# Ada_-_Base_Block_-_Microcontroller_Issue.net
KiCad netlist of a schematic drawn in Altium Designer
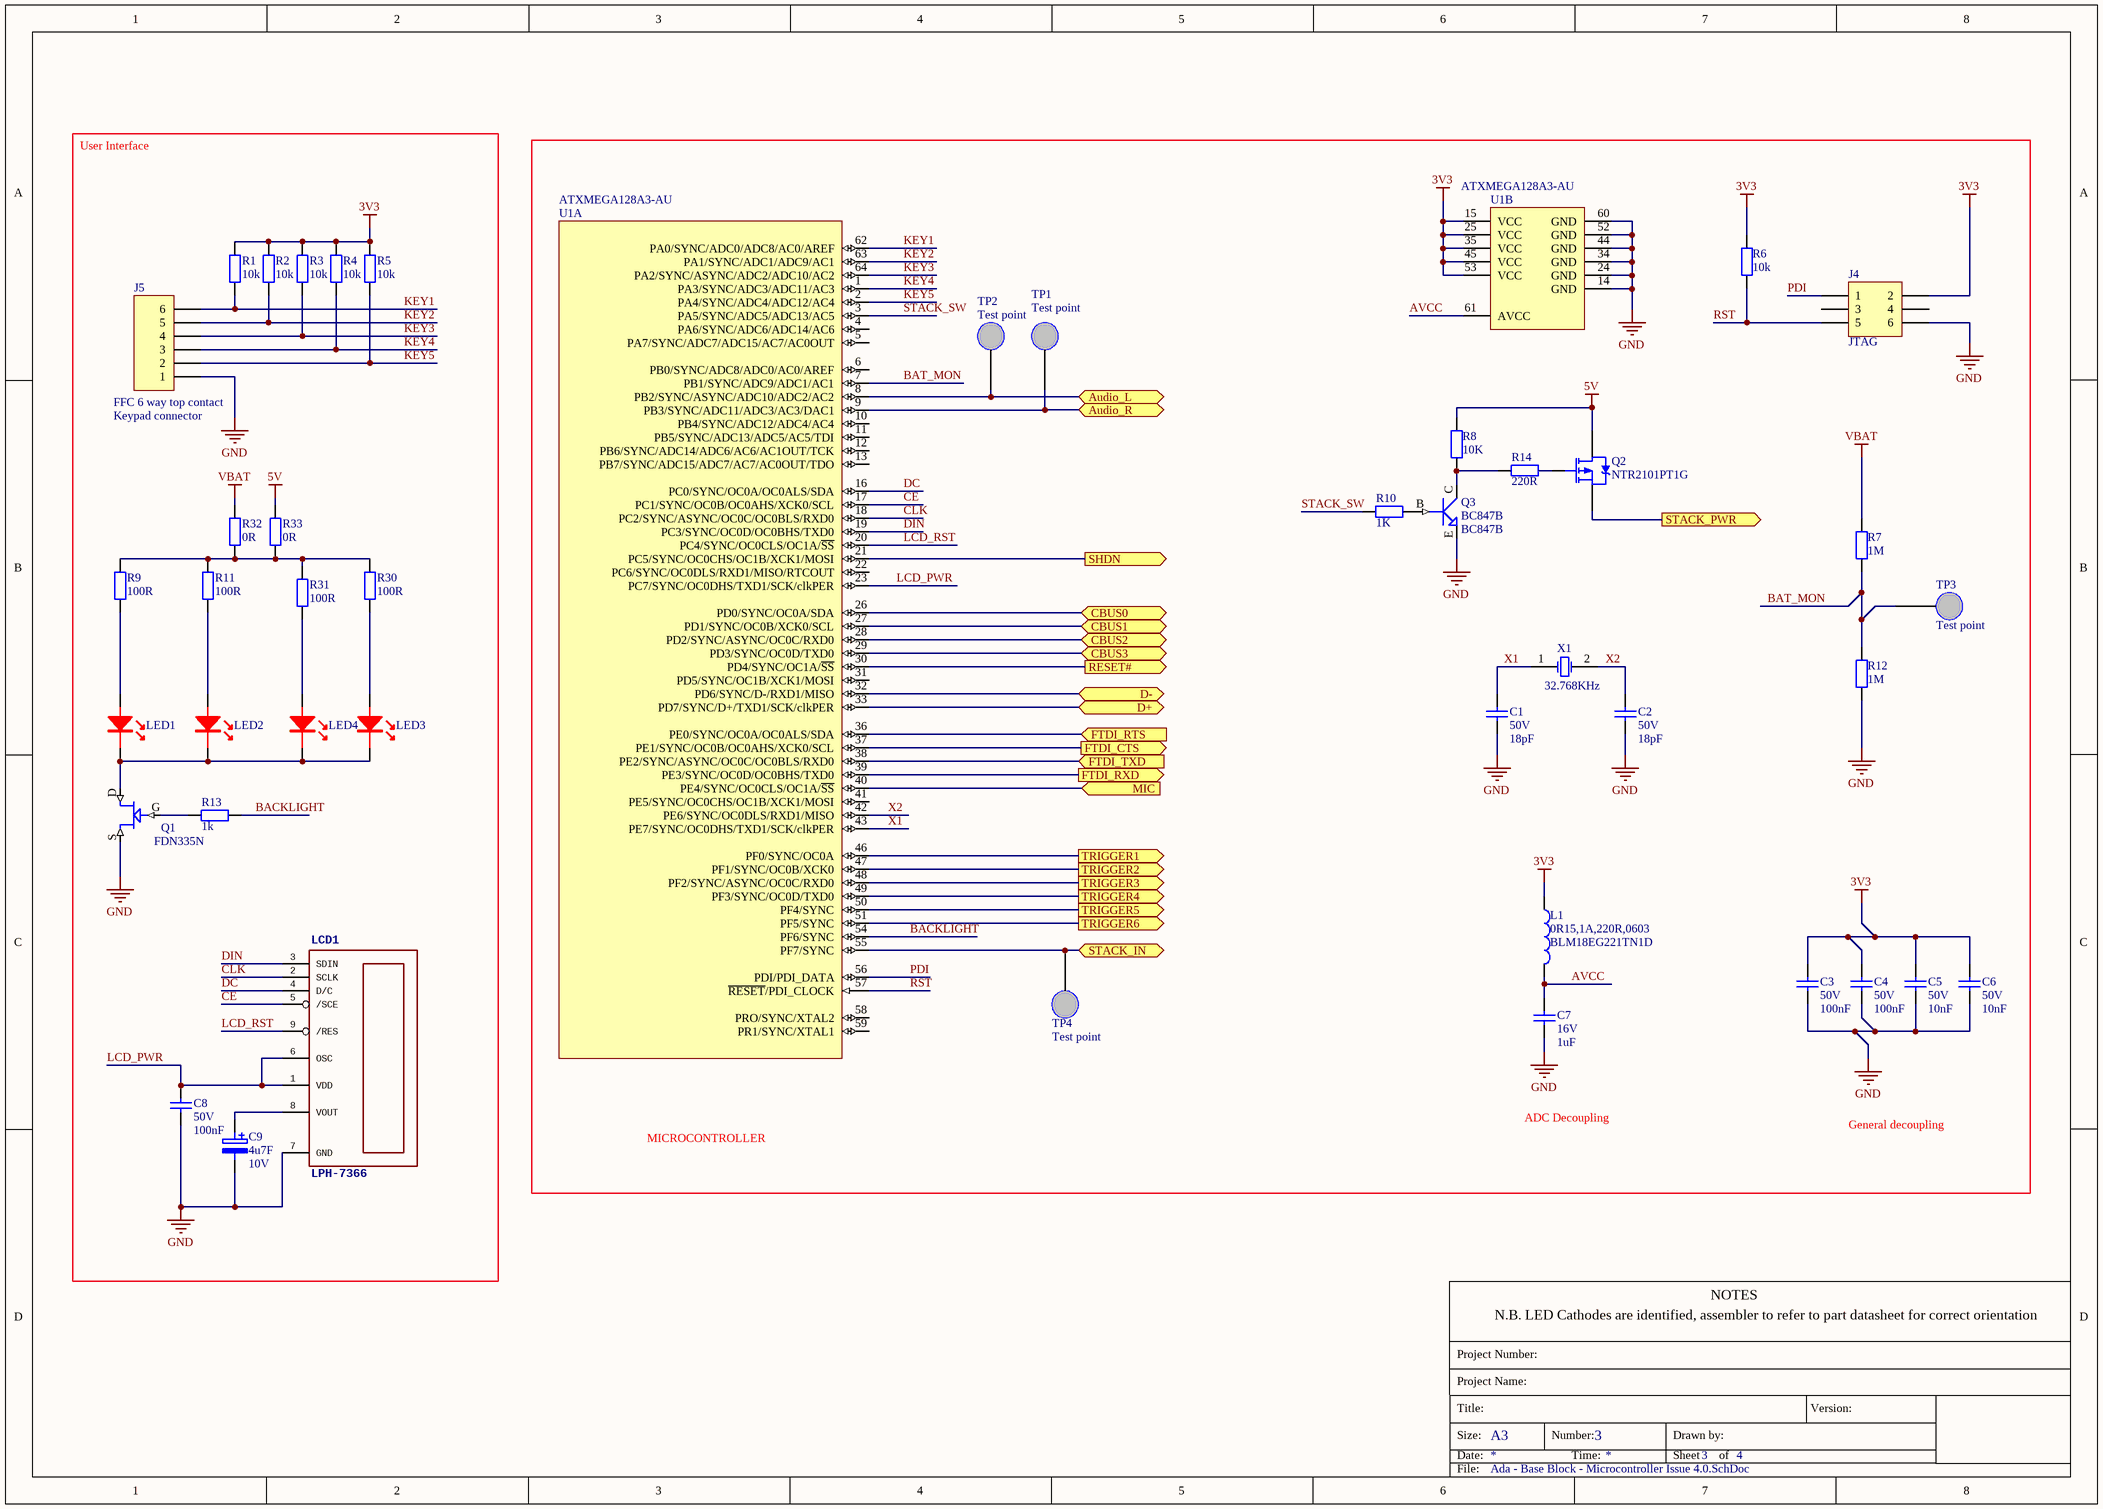
[diagram p0: Ada - Base Block - Microcontroller Issue 4.0.SchDoc]

(export (version "E")
  (design (tool "Eeschema 10.0.6"))
  (components
    (comp (ref "C1")
      (value "18pF")
      (footprint "C0603")
      (description "Ceramic")
      (fields
        (field (name "MANUFACTURER") "KEMET")
        (field (name "MANUF PART #") "C0603C180J5GAC")
        (field (name "VOLTAGE") "50V")
      )
      (libsource (lib "Capacitors") (part "18pF, 50V, 0603"))
    )
    (comp (ref "C2")
      (value "18pF")
      (footprint "C0603")
      (description "Ceramic")
      (fields
        (field (name "MANUFACTURER") "KEMET")
        (field (name "MANUF PART #") "C0603C180J5GAC")
        (field (name "VOLTAGE") "50V")
      )
      (libsource (lib "Capacitors") (part "18pF, 50V, 0603"))
    )
    (comp (ref "C3")
      (value "100nF")
      (footprint "C0603")
      (description "Ceramic")
      (fields
        (field (name "MANUFACTURER") "TruCap")
        (field (name "MANUF PART #") "U0603R103")
        (field (name "VOLTAGE") "50V")
      )
      (libsource (lib "Capacitors") (part "100nF, 16V, 0603"))
    )
    (comp (ref "C4")
      (value "100nF")
      (footprint "C0603")
      (description "Ceramic")
      (fields
        (field (name "MANUFACTURER") "TruCap")
        (field (name "MANUF PART #") "U0603R103")
        (field (name "VOLTAGE") "50V")
      )
      (libsource (lib "Capacitors") (part "100nF, 16V, 0603"))
    )
    (comp (ref "C5")
      (value "10nF")
      (footprint "C0603")
      (description "Ceramic")
      (fields
        (field (name "MANUFACTURER") "MULTICOMP")
        (field (name "MANUF PART #") "MCCA000238")
        (field (name "VOLTAGE") "50V")
      )
      (libsource (lib "Capacitors") (part "10nF, 50V, 0603"))
    )
    (comp (ref "C6")
      (value "10nF")
      (footprint "C0603")
      (description "Ceramic")
      (fields
        (field (name "MANUFACTURER") "MULTICOMP")
        (field (name "MANUF PART #") "MCCA000238")
        (field (name "VOLTAGE") "50V")
      )
      (libsource (lib "Capacitors") (part "10nF, 50V, 0603"))
    )
    (comp (ref "C7")
      (value "1uF")
      (footprint "C0603")
      (description "Ceramic")
      (fields
        (field (name "MANUFACTURER") "KEMET")
        (field (name "MANUF PART #") "C0603C105K4PAC")
        (field (name "VOLTAGE") "16V")
      )
      (libsource (lib "Capacitors") (part "1uF, 16V, 0603"))
    )
    (comp (ref "C8")
      (value "100nF")
      (footprint "C0603")
      (description "Ceramic")
      (fields
        (field (name "MANUFACTURER") "TruCap")
        (field (name "MANUF PART #") "U0603R103")
        (field (name "VOLTAGE") "50V")
      )
      (libsource (lib "Capacitors") (part "100nF, 16V, 0603"))
    )
    (comp (ref "C9")
      (value "4u7F")
      (footprint "KEMET CASE A")
      (description "Tantalum")
      (fields
        (field (name "MANUFACTURER") "KEMET")
        (field (name "MANUF PART #") "T491A475K010AT")
        (field (name "VOLTAGE") "10V")
      )
      (libsource (lib "Capacitors") (part "4U7F, 10V, case_a"))
    )
    (comp (ref "J4")
      (value "JTAG")
      (footprint "HDR2X3")
      (description "Header, 15-Pin, Dual row")
      (fields (field (name "MANUFACTURER") "TruConnect") (field (name "PART NO.") "22-0500"))
      (libsource (lib "Connectors") (part "Header 2x3"))
    )
    (comp (ref "J5")
      (value "Keypad connector")
      (footprint "HLW6R-2C7LF")
      (description "Header, 6-Pin")
      (fields
        (field (name "MANUFACTURER") "FCI")
        (field (name "MANUF PART #") "HLW6R-2C7LF")
        (field (name "ALTIUM_VALUE") "FFC 6 way top contact")
      )
      (libsource (lib "Connectors") (part "Header 6"))
    )
    (comp (ref "L1")
      (value "0R15,1A,220R,0603")
      (footprint "L0603")
      (description "FERRITE BEAD")
      (fields
        (field (name "MANUFACTURER") "MURATA")
        (field (name "MANUF PART #") "BLM18EG221TN1D")
        (field (name "ALTIUM_VALUE") "BLM18EG221TN1D")
      )
      (libsource (lib "Inductors") (part "0R15,1A,220R,0603"))
    )
    (comp (ref "LCD1")
      (value "LPH-7366")
      (footprint "LPH-7366")
      (fields
        (field (name "MANUFACTURER") "Na")
        (field (name "MANUF PART #") "na")
        (field (name "PART NO.") "LPH7366-1")
      )
      (libsource (lib "LCD") (part "LPH-7366"))
    )
    (comp (ref "LED1")
      (value "LED RED 0805 SUPER-RED")
      (footprint "LED, RED, 0805")
      (description "LED, SMD, 0805, SUPER-RED")
      (fields (field (name "MANUFACTURER") "MULTICOMP") (field (name "MANUF PART #") "MCL-S270SRC"))
      (libsource (lib "Diodes") (part "LED RED 0805 SUPER-RED"))
    )
    (comp (ref "LED2")
      (value "LED RED 0805 SUPER-RED")
      (footprint "LED, RED, 0805")
      (description "LED, SMD, 0805, SUPER-RED")
      (fields (field (name "MANUFACTURER") "MULTICOMP") (field (name "MANUF PART #") "MCL-S270SRC"))
      (libsource (lib "Diodes") (part "LED RED 0805 SUPER-RED"))
    )
    (comp (ref "LED3")
      (value "LED RED 0805 SUPER-RED")
      (footprint "LED, RED, 0805")
      (description "LED, SMD, 0805, SUPER-RED")
      (fields (field (name "MANUFACTURER") "MULTICOMP") (field (name "MANUF PART #") "MCL-S270SRC"))
      (libsource (lib "Diodes") (part "LED RED 0805 SUPER-RED"))
    )
    (comp (ref "LED4")
      (value "LED RED 0805 SUPER-RED")
      (footprint "LED, RED, 0805")
      (description "LED, SMD, 0805, SUPER-RED")
      (fields (field (name "MANUFACTURER") "MULTICOMP") (field (name "MANUF PART #") "MCL-S270SRC"))
      (libsource (lib "Diodes") (part "LED RED 0805 SUPER-RED"))
    )
    (comp (ref "Q1")
      (value "FDN335N")
      (footprint "SOT-23")
      (fields (field (name "MANUFACTURER") "FAIRCHILD SEMICONDUCTOR") (field (name "PART NO.") "9845348RL"))
      (libsource (lib "Transistors and FETs") (part "FDN335N"))
    )
    (comp (ref "Q2")
      (value "NTR2101PT1G")
      (footprint "SOT-23 DIODE - duplicate")
      (description "P-Channel Power MOSFET")
      (fields (field (name "MANUFACTURER") "ON SEMICONDUCTOR") (field (name "VOLTAGE") "8V"))
      (libsource (lib "Transistors and FETs") (part "PMOS-2"))
    )
    (comp (ref "Q3")
      (value "BC847B")
      (footprint "SOT-23T")
      (fields (field (name "ALTIUM_VALUE") "BC847B"))
      (libsource (lib "Transistors and FETs") (part "BC847B"))
    )
    (comp (ref "R1")
      (value "10k")
      (footprint "R0603")
      (description "Resistor 0603")
      (libsource (lib "Passives Rev B") (part "Resistor 0603"))
    )
    (comp (ref "R2")
      (value "10k")
      (footprint "R0603")
      (description "Resistor 0603")
      (libsource (lib "Passives Rev B") (part "Resistor 0603"))
    )
    (comp (ref "R3")
      (value "10k")
      (footprint "R0603")
      (description "Resistor 0603")
      (libsource (lib "Passives Rev B") (part "Resistor 0603"))
    )
    (comp (ref "R4")
      (value "10k")
      (footprint "R0603")
      (description "Resistor 0603")
      (libsource (lib "Passives Rev B") (part "Resistor 0603"))
    )
    (comp (ref "R5")
      (value "10k")
      (footprint "R0603")
      (description "Resistor 0603")
      (libsource (lib "Passives Rev B") (part "Resistor 0603"))
    )
    (comp (ref "R6")
      (value "10k")
      (footprint "R0603")
      (description "Resistor 0603")
      (libsource (lib "Passives Rev B") (part "Resistor 0603"))
    )
    (comp (ref "R7")
      (value "1M")
      (footprint "R0603")
      (description "Resistor 0603")
      (libsource (lib "Passives Rev B") (part "Resistor 0603"))
    )
    (comp (ref "R8")
      (value "10K")
      (footprint "R0603")
      (description "Resistor 0603")
      (libsource (lib "") (part "Resistor 0603_1"))
    )
    (comp (ref "R9")
      (value "100R")
      (footprint "R0603")
      (description "Resistor 0603")
      (libsource (lib "Passives Rev B") (part "Resistor 0603"))
    )
    (comp (ref "R10")
      (value "1K")
      (footprint "R0603")
      (description "Resistor 0603")
      (libsource (lib "") (part "Resistor 0603_2"))
    )
    (comp (ref "R11")
      (value "100R")
      (footprint "R0603")
      (description "Resistor 0603")
      (libsource (lib "Passives Rev B") (part "Resistor 0603"))
    )
    (comp (ref "R12")
      (value "1M")
      (footprint "R0603")
      (description "Resistor 0603")
      (libsource (lib "Passives Rev B") (part "Resistor 0603"))
    )
    (comp (ref "R13")
      (value "1k")
      (footprint "R0603")
      (description "Resistor 0603")
      (libsource (lib "") (part "Resistor 0603_1"))
    )
    (comp (ref "R14")
      (value "220R")
      (footprint "R0603")
      (description "Resistor 0603")
      (libsource (lib "") (part "Resistor 0603_2"))
    )
    (comp (ref "R30")
      (value "100R")
      (footprint "R0603")
      (description "Resistor 0603")
      (libsource (lib "Passives Rev B") (part "Resistor 0603"))
    )
    (comp (ref "R31")
      (value "100R")
      (footprint "R0603")
      (description "Resistor 0603")
      (libsource (lib "Passives Rev B") (part "Resistor 0603"))
    )
    (comp (ref "R32")
      (value "0R")
      (footprint "R0603")
      (description "Resistor 0603")
      (libsource (lib "Passives Rev B") (part "Resistor 0603"))
    )
    (comp (ref "R33")
      (value "0R")
      (footprint "R0603")
      (description "Resistor 0603")
      (libsource (lib "Passives Rev B") (part "Resistor 0603"))
    )
    (comp (ref "TP1")
      (value "Test point")
      (footprint "TP")
      (description "Test Point")
      (libsource (lib "General") (part "Test point"))
    )
    (comp (ref "TP2")
      (value "Test point")
      (footprint "TP")
      (description "Test Point")
      (libsource (lib "General") (part "Test point"))
    )
    (comp (ref "TP3")
      (value "Test point")
      (footprint "TP")
      (description "Test Point")
      (libsource (lib "General") (part "Test point"))
    )
    (comp (ref "TP4")
      (value "Test point")
      (footprint "TP")
      (description "Test Point")
      (libsource (lib "General") (part "Test point"))
    )
    (comp (ref "U1")
      (value "ATXMEGA128A3-AU")
      (footprint "64A_N")
      (fields (field (name "MANUFACTURER") "ATMEL") (field (name "PART NO.") "1748550"))
      (libsource (lib "Atmel Microcontroller AVR XMEGA") (part "ATxmega256A3U-AU"))
    )
    (comp (ref "X1")
      (value "32.768KHz")
      (footprint "FC 13F")
      (description "Crystal Oscillator, 32.768KHZ")
      (fields
        (field (name "MANUFACTURER") "EPSON TOYOCOM")
        (field (name "MANUF PART #") "FC-13F,32.768KHZ, 12.5PF")
      )
      (libsource (lib "General") (part "XTAL 32.768KHZ"))
    )
  )
  (nets
    (net (code "1") (name "/AVCC") (class "Default")
      (node (ref "C7") (pin "2") (pinfunction "2_2") (pintype "passive"))
      (node (ref "L1") (pin "2") (pinfunction "2_2") (pintype "passive"))
      (node (ref "U1") (pin "61") (pinfunction "AVCC_61") (pintype "power_in"))
    )
    (net (code "2") (name "/Audio_L") (class "Default")
      (node (ref "TP2") (pin "1") (pinfunction "1_1") (pintype "passive"))
      (node (ref "U1") (pin "8") (pinfunction "PB2/SYNC/ASYNC/ADC10/ADC2/AC2_8") (pintype "bidirectional"))
    )
    (net (code "3") (name "/Audio_R") (class "Default")
      (node (ref "TP1") (pin "1") (pinfunction "1_1") (pintype "passive"))
      (node (ref "U1") (pin "9") (pinfunction "PB3/SYNC/ADC11/ADC3/AC3/DAC1_9") (pintype "bidirectional"))
    )
    (net (code "4") (name "/BACKLIGHT") (class "Default")
      (node (ref "R13") (pin "1") (pinfunction "1_1") (pintype "passive"))
      (node (ref "U1") (pin "54") (pinfunction "PF6/SYNC_54") (pintype "bidirectional"))
    )
    (net (code "5") (name "/BAT_MON") (class "Default")
      (node (ref "R12") (pin "2") (pinfunction "2_2") (pintype "passive"))
      (node (ref "R7") (pin "1") (pinfunction "1_1") (pintype "passive"))
      (node (ref "TP3") (pin "1") (pinfunction "1_1") (pintype "passive"))
      (node (ref "U1") (pin "7") (pinfunction "PB1/SYNC/ADC9/ADC1/AC1_7") (pintype "bidirectional"))
    )
    (net (code "6") (name "/CBUS0") (class "Default")
      (node (ref "U1") (pin "26") (pinfunction "PD0/SYNC/OC0A/SDA_26") (pintype "bidirectional"))
    )
    (net (code "7") (name "/CBUS1") (class "Default")
      (node (ref "U1") (pin "27") (pinfunction "PD1/SYNC/OC0B/XCK0/SCL_27") (pintype "bidirectional"))
    )
    (net (code "8") (name "/CBUS2") (class "Default")
      (node (ref "U1") (pin "28") (pinfunction "PD2/SYNC/ASYNC/OC0C/RXD0_28") (pintype "bidirectional"))
    )
    (net (code "9") (name "/CBUS3") (class "Default")
      (node (ref "U1") (pin "29") (pinfunction "PD3/SYNC/OC0D/TXD0_29") (pintype "bidirectional"))
    )
    (net (code "10") (name "/CE") (class "Default")
      (node (ref "LCD1") (pin "5") (pinfunction "/SCE_5") (pintype "passive"))
      (node (ref "U1") (pin "17") (pinfunction "PC1/SYNC/OC0B/OC0AHS/XCK0/SCL_17") (pintype "bidirectional"))
    )
    (net (code "11") (name "/CLK") (class "Default")
      (node (ref "LCD1") (pin "2") (pinfunction "SCLK_2") (pintype "passive"))
      (node (ref "U1") (pin "18") (pinfunction "PC2/SYNC/ASYNC/OC0C/OC0BLS/RXD0_18") (pintype "bidirectional"))
    )
    (net (code "12") (name "/D+") (class "Default")
      (node (ref "U1") (pin "33") (pinfunction "PD7/SYNC/D+/TXD1/SCK/clkPER_33") (pintype "bidirectional"))
    )
    (net (code "13") (name "/D-") (class "Default")
      (node (ref "U1") (pin "32") (pinfunction "PD6/SYNC/D-/RXD1/MISO_32") (pintype "bidirectional"))
    )
    (net (code "14") (name "/DC") (class "Default")
      (node (ref "LCD1") (pin "4") (pinfunction "D/C_4") (pintype "passive"))
      (node (ref "U1") (pin "16") (pinfunction "PC0/SYNC/OC0A/OC0ALS/SDA_16") (pintype "bidirectional"))
    )
    (net (code "15") (name "/DIN") (class "Default")
      (node (ref "LCD1") (pin "3") (pinfunction "SDIN_3") (pintype "passive"))
      (node (ref "U1") (pin "19") (pinfunction "PC3/SYNC/OC0D/OC0BHS/TXD0_19") (pintype "bidirectional"))
    )
    (net (code "16") (name "/FTDI_CTS") (class "Default")
      (node (ref "U1") (pin "37") (pinfunction "PE1/SYNC/OC0B/OC0AHS/XCK0/SCL_37") (pintype "bidirectional"))
    )
    (net (code "17") (name "/FTDI_RTS") (class "Default")
      (node (ref "U1") (pin "36") (pinfunction "PE0/SYNC/OC0A/OC0ALS/SDA_36") (pintype "bidirectional"))
    )
    (net (code "18") (name "/FTDI_RXD") (class "Default")
      (node (ref "U1") (pin "39") (pinfunction "PE3/SYNC/OC0D/OC0BHS/TXD0_39") (pintype "bidirectional"))
    )
    (net (code "19") (name "/FTDI_TXD") (class "Default")
      (node (ref "U1") (pin "38") (pinfunction "PE2/SYNC/ASYNC/OC0C/OC0BLS/RXD0_38") (pintype "bidirectional"))
    )
    (net (code "20") (name "/KEY1") (class "Default")
      (node (ref "J5") (pin "6") (pinfunction "6_6") (pintype "passive"))
      (node (ref "R1") (pin "1") (pinfunction "1_1") (pintype "passive"))
      (node (ref "U1") (pin "62") (pinfunction "PA0/SYNC/ADC0/ADC8/AC0/AREF_62") (pintype "bidirectional"))
    )
    (net (code "21") (name "/KEY2") (class "Default")
      (node (ref "J5") (pin "5") (pinfunction "5_5") (pintype "passive"))
      (node (ref "R2") (pin "1") (pinfunction "1_1") (pintype "passive"))
      (node (ref "U1") (pin "63") (pinfunction "PA1/SYNC/ADC1/ADC9/AC1_63") (pintype "bidirectional"))
    )
    (net (code "22") (name "/KEY3") (class "Default")
      (node (ref "J5") (pin "4") (pinfunction "4_4") (pintype "passive"))
      (node (ref "R3") (pin "1") (pinfunction "1_1") (pintype "passive"))
      (node (ref "U1") (pin "64") (pinfunction "PA2/SYNC/ASYNC/ADC2/ADC10/AC2_64") (pintype "bidirectional"))
    )
    (net (code "23") (name "/KEY4") (class "Default")
      (node (ref "J5") (pin "3") (pinfunction "3_3") (pintype "passive"))
      (node (ref "R4") (pin "1") (pinfunction "1_1") (pintype "passive"))
      (node (ref "U1") (pin "1") (pinfunction "PA3/SYNC/ADC3/ADC11/AC3_1") (pintype "bidirectional"))
    )
    (net (code "24") (name "/KEY5") (class "Default")
      (node (ref "J5") (pin "2") (pinfunction "2_2") (pintype "passive"))
      (node (ref "R5") (pin "1") (pinfunction "1_1") (pintype "passive"))
      (node (ref "U1") (pin "2") (pinfunction "PA4/SYNC/ADC4/ADC12/AC4_2") (pintype "bidirectional"))
    )
    (net (code "25") (name "/LCD_PWR") (class "Default")
      (node (ref "C8") (pin "2") (pinfunction "2_2") (pintype "passive"))
      (node (ref "LCD1") (pin "1") (pinfunction "VDD_1") (pintype "power_in"))
      (node (ref "LCD1") (pin "6") (pinfunction "OSC_6") (pintype "passive"))
      (node (ref "U1") (pin "23") (pinfunction "PC7/SYNC/OC0DHS/TXD1/SCK/clkPER_23") (pintype "bidirectional"))
    )
    (net (code "26") (name "/LCD_RST") (class "Default")
      (node (ref "LCD1") (pin "9") (pinfunction "/RES_9") (pintype "passive"))
      (node (ref "U1") (pin "20") (pinfunction "PC4/SYNC/OC0CLS/OC1A/~{SS}_20") (pintype "bidirectional"))
    )
    (net (code "27") (name "/MIC") (class "Default")
      (node (ref "U1") (pin "40") (pinfunction "PE4/SYNC/OC0CLS/OC1A/~{SS}_40") (pintype "bidirectional"))
    )
    (net (code "28") (name "/PDI") (class "Default")
      (node (ref "J4") (pin "1") (pinfunction "1_1") (pintype "passive"))
      (node (ref "U1") (pin "56") (pinfunction "PDI/PDI_DATA_56") (pintype "bidirectional"))
    )
    (net (code "29") (name "/RESET#") (class "Default")
      (node (ref "U1") (pin "30") (pinfunction "PD4/SYNC/OC1A/~{SS}_30") (pintype "bidirectional"))
    )
    (net (code "30") (name "/RST") (class "Default")
      (node (ref "J4") (pin "5") (pinfunction "5_5") (pintype "passive"))
      (node (ref "R6") (pin "1") (pinfunction "1_1") (pintype "passive"))
      (node (ref "U1") (pin "57") (pinfunction "~{RESET}/PDI_CLOCK_57") (pintype "input"))
    )
    (net (code "31") (name "/SHDN") (class "Default")
      (node (ref "U1") (pin "21") (pinfunction "PC5/SYNC/OC0CHS/OC1B/XCK1/MOSI_21") (pintype "bidirectional"))
    )
    (net (code "32") (name "/STACK_IN") (class "Default")
      (node (ref "TP4") (pin "1") (pinfunction "1_1") (pintype "passive"))
      (node (ref "U1") (pin "55") (pinfunction "PF7/SYNC_55") (pintype "bidirectional"))
    )
    (net (code "33") (name "/STACK_PWR") (class "Default")
      (node (ref "Q2") (pin "3") (pinfunction "D_3") (pintype "passive"))
    )
    (net (code "34") (name "/STACK_SW") (class "Default")
      (node (ref "R10") (pin "1") (pinfunction "1_1") (pintype "passive"))
      (node (ref "U1") (pin "3") (pinfunction "PA5/SYNC/ADC5/ADC13/AC5_3") (pintype "bidirectional"))
    )
    (net (code "35") (name "/TRIGGER1") (class "Default")
      (node (ref "U1") (pin "46") (pinfunction "PF0/SYNC/OC0A_46") (pintype "bidirectional"))
    )
    (net (code "36") (name "/TRIGGER2") (class "Default")
      (node (ref "U1") (pin "47") (pinfunction "PF1/SYNC/OC0B/XCK0_47") (pintype "bidirectional"))
    )
    (net (code "37") (name "/TRIGGER3") (class "Default")
      (node (ref "U1") (pin "48") (pinfunction "PF2/SYNC/ASYNC/OC0C/RXD0_48") (pintype "bidirectional"))
    )
    (net (code "38") (name "/TRIGGER4") (class "Default")
      (node (ref "U1") (pin "49") (pinfunction "PF3/SYNC/OC0D/TXD0_49") (pintype "bidirectional"))
    )
    (net (code "39") (name "/TRIGGER5") (class "Default")
      (node (ref "U1") (pin "50") (pinfunction "PF4/SYNC_50") (pintype "bidirectional"))
    )
    (net (code "40") (name "/TRIGGER6") (class "Default")
      (node (ref "U1") (pin "51") (pinfunction "PF5/SYNC_51") (pintype "bidirectional"))
    )
    (net (code "41") (name "/X1") (class "Default")
      (node (ref "C1") (pin "2") (pinfunction "2_2") (pintype "passive"))
      (node (ref "U1") (pin "43") (pinfunction "PE7/SYNC/OC0DHS/TXD1/SCK/clkPER_43") (pintype "bidirectional"))
      (node (ref "X1") (pin "1") (pinfunction "OSC1_1") (pintype "passive"))
    )
    (net (code "42") (name "/X2") (class "Default")
      (node (ref "C2") (pin "2") (pinfunction "2_2") (pintype "passive"))
      (node (ref "U1") (pin "42") (pinfunction "PE6/SYNC/OC0DLS/RXD1/MISO_42") (pintype "bidirectional"))
      (node (ref "X1") (pin "2") (pinfunction "OSC2_2") (pintype "passive"))
    )
    (net (code "43") (name "3V3") (class "Default")
      (node (ref "C3") (pin "2") (pinfunction "2_2") (pintype "passive"))
      (node (ref "C4") (pin "2") (pinfunction "2_2") (pintype "passive"))
      (node (ref "C5") (pin "2") (pinfunction "2_2") (pintype "passive"))
      (node (ref "C6") (pin "2") (pinfunction "2_2") (pintype "passive"))
      (node (ref "J4") (pin "2") (pinfunction "2_2") (pintype "passive"))
      (node (ref "L1") (pin "1") (pinfunction "1_1") (pintype "passive"))
      (node (ref "R1") (pin "2") (pinfunction "2_2") (pintype "passive"))
      (node (ref "R2") (pin "2") (pinfunction "2_2") (pintype "passive"))
      (node (ref "R3") (pin "2") (pinfunction "2_2") (pintype "passive"))
      (node (ref "R4") (pin "2") (pinfunction "2_2") (pintype "passive"))
      (node (ref "R5") (pin "2") (pinfunction "2_2") (pintype "passive"))
      (node (ref "R6") (pin "2") (pinfunction "2_2") (pintype "passive"))
      (node (ref "U1") (pin "15") (pinfunction "VCC_15") (pintype "power_in"))
      (node (ref "U1") (pin "25") (pinfunction "VCC_25") (pintype "power_in"))
      (node (ref "U1") (pin "35") (pinfunction "VCC_35") (pintype "power_in"))
      (node (ref "U1") (pin "45") (pinfunction "VCC_45") (pintype "power_in"))
      (node (ref "U1") (pin "53") (pinfunction "VCC_53") (pintype "power_in"))
    )
    (net (code "44") (name "5V") (class "Default")
      (node (ref "Q2") (pin "2") (pinfunction "S_2") (pintype "passive"))
      (node (ref "R33") (pin "2") (pinfunction "2_2") (pintype "passive"))
      (node (ref "R8") (pin "1") (pinfunction "1_1") (pintype "passive"))
    )
    (net (code "45") (name "GND") (class "Default")
      (node (ref "C1") (pin "1") (pinfunction "1_1") (pintype "passive"))
      (node (ref "C2") (pin "1") (pinfunction "1_1") (pintype "passive"))
      (node (ref "C3") (pin "1") (pinfunction "1_1") (pintype "passive"))
      (node (ref "C4") (pin "1") (pinfunction "1_1") (pintype "passive"))
      (node (ref "C5") (pin "1") (pinfunction "1_1") (pintype "passive"))
      (node (ref "C6") (pin "1") (pinfunction "1_1") (pintype "passive"))
      (node (ref "C7") (pin "1") (pinfunction "1_1") (pintype "passive"))
      (node (ref "C8") (pin "1") (pinfunction "1_1") (pintype "passive"))
      (node (ref "C9") (pin "2") (pinfunction "2_2") (pintype "passive"))
      (node (ref "J4") (pin "6") (pinfunction "6_6") (pintype "passive"))
      (node (ref "J5") (pin "1") (pinfunction "1_1") (pintype "passive"))
      (node (ref "LCD1") (pin "7") (pinfunction "GND_7") (pintype "power_in"))
      (node (ref "Q1") (pin "S") (pinfunction "S_S") (pintype "input"))
      (node (ref "Q3") (pin "E") (pinfunction "EMITTER_E") (pintype "passive"))
      (node (ref "R12") (pin "1") (pinfunction "1_1") (pintype "passive"))
      (node (ref "U1") (pin "14") (pinfunction "GND_14") (pintype "power_in"))
      (node (ref "U1") (pin "24") (pinfunction "GND_24") (pintype "power_in"))
      (node (ref "U1") (pin "34") (pinfunction "GND_34") (pintype "power_in"))
      (node (ref "U1") (pin "44") (pinfunction "GND_44") (pintype "power_in"))
      (node (ref "U1") (pin "52") (pinfunction "GND_52") (pintype "power_in"))
      (node (ref "U1") (pin "60") (pinfunction "GND_60") (pintype "power_in"))
    )
    (net (code "46") (name "Net-(LCD1-VOUT)") (class "Default")
      (node (ref "C9") (pin "1") (pinfunction "1_1") (pintype "passive"))
      (node (ref "LCD1") (pin "8") (pinfunction "VOUT_8") (pintype "passive"))
    )
    (net (code "47") (name "Net-(LED1-PadA)") (class "Default")
      (node (ref "LED1") (pin "A") (pinfunction "A_A") (pintype "passive"))
      (node (ref "R9") (pin "1") (pinfunction "1_1") (pintype "passive"))
    )
    (net (code "48") (name "Net-(LED1-PadK)") (class "Default")
      (node (ref "LED1") (pin "K") (pinfunction "K_K") (pintype "passive"))
      (node (ref "LED2") (pin "K") (pinfunction "K_K") (pintype "passive"))
      (node (ref "LED3") (pin "K") (pinfunction "K_K") (pintype "passive"))
      (node (ref "LED4") (pin "K") (pinfunction "K_K") (pintype "passive"))
      (node (ref "Q1") (pin "D") (pinfunction "D_D") (pintype "input"))
    )
    (net (code "49") (name "Net-(LED2-PadA)") (class "Default")
      (node (ref "LED2") (pin "A") (pinfunction "A_A") (pintype "passive"))
      (node (ref "R11") (pin "1") (pinfunction "1_1") (pintype "passive"))
    )
    (net (code "50") (name "Net-(LED3-PadA)") (class "Default")
      (node (ref "LED3") (pin "A") (pinfunction "A_A") (pintype "passive"))
      (node (ref "R30") (pin "1") (pinfunction "1_1") (pintype "passive"))
    )
    (net (code "51") (name "Net-(LED4-PadA)") (class "Default")
      (node (ref "LED4") (pin "A") (pinfunction "A_A") (pintype "passive"))
      (node (ref "R31") (pin "1") (pinfunction "1_1") (pintype "passive"))
    )
    (net (code "52") (name "Net-(Q1-PadG)") (class "Default")
      (node (ref "Q1") (pin "G") (pinfunction "G_G") (pintype "input"))
      (node (ref "R13") (pin "2") (pinfunction "2_2") (pintype "passive"))
    )
    (net (code "53") (name "Net-(Q2-G)") (class "Default")
      (node (ref "Q2") (pin "1") (pinfunction "G_1") (pintype "passive"))
      (node (ref "R14") (pin "2") (pinfunction "2_2") (pintype "passive"))
    )
    (net (code "54") (name "Net-(Q3-BASE)") (class "Default")
      (node (ref "Q3") (pin "B") (pinfunction "BASE_B") (pintype "input"))
      (node (ref "R10") (pin "2") (pinfunction "2_2") (pintype "passive"))
    )
    (net (code "55") (name "Net-(Q3-COLLECTOR)") (class "Default")
      (node (ref "Q3") (pin "C") (pinfunction "COLLECTOR_C") (pintype "passive"))
      (node (ref "R14") (pin "1") (pinfunction "1_1") (pintype "passive"))
      (node (ref "R8") (pin "2") (pinfunction "2_2") (pintype "passive"))
    )
    (net (code "56") (name "Net-(R11-Pad2)") (class "Default")
      (node (ref "R11") (pin "2") (pinfunction "2_2") (pintype "passive"))
      (node (ref "R30") (pin "2") (pinfunction "2_2") (pintype "passive"))
      (node (ref "R31") (pin "2") (pinfunction "2_2") (pintype "passive"))
      (node (ref "R32") (pin "1") (pinfunction "1_1") (pintype "passive"))
      (node (ref "R33") (pin "1") (pinfunction "1_1") (pintype "passive"))
      (node (ref "R9") (pin "2") (pinfunction "2_2") (pintype "passive"))
    )
    (net (code "57") (name "VBAT") (class "Default")
      (node (ref "R32") (pin "2") (pinfunction "2_2") (pintype "passive"))
      (node (ref "R7") (pin "2") (pinfunction "2_2") (pintype "passive"))
    )
    (net (code "58") (name "unconnected-(J4-Pad3)") (class "Default")
      (node (ref "J4") (pin "3") (pinfunction "3_3") (pintype "passive"))
    )
    (net (code "59") (name "unconnected-(J4-Pad4)") (class "Default")
      (node (ref "J4") (pin "4") (pinfunction "4_4") (pintype "passive"))
    )
    (net (code "60") (name "unconnected-(U1A-PA6{slash}SYNC{slash}ADC6{slash}ADC14{slash}AC6-Pad4)") (class "Default")
      (node (ref "U1") (pin "4") (pinfunction "PA6/SYNC/ADC6/ADC14/AC6_4") (pintype "bidirectional"))
    )
    (net (code "61") (name "unconnected-(U1A-PA7{slash}SYNC{slash}ADC7{slash}ADC15{slash}AC7{slash}AC0OUT-Pad5)") (class "Default")
      (node (ref "U1") (pin "5") (pinfunction "PA7/SYNC/ADC7/ADC15/AC7/AC0OUT_5") (pintype "bidirectional"))
    )
    (net (code "62") (name "unconnected-(U1A-PB0{slash}SYNC{slash}ADC8{slash}ADC0{slash}AC0{slash}AREF-Pad6)") (class "Default")
      (node (ref "U1") (pin "6") (pinfunction "PB0/SYNC/ADC8/ADC0/AC0/AREF_6") (pintype "bidirectional"))
    )
    (net (code "63") (name "unconnected-(U1A-PB4{slash}SYNC{slash}ADC12{slash}ADC4{slash}AC4-Pad10)") (class "Default")
      (node (ref "U1") (pin "10") (pinfunction "PB4/SYNC/ADC12/ADC4/AC4_10") (pintype "bidirectional"))
    )
    (net (code "64") (name "unconnected-(U1A-PB5{slash}SYNC{slash}ADC13{slash}ADC5{slash}AC5{slash}TDI-Pad11)") (class "Default")
      (node (ref "U1") (pin "11") (pinfunction "PB5/SYNC/ADC13/ADC5/AC5/TDI_11") (pintype "bidirectional"))
    )
    (net (code "65") (name "unconnected-(U1A-PB6{slash}SYNC{slash}ADC14{slash}ADC6{slash}AC6{slash}AC1OUT{slash}TCK-Pad12)") (class "Default")
      (node (ref "U1") (pin "12") (pinfunction "PB6/SYNC/ADC14/ADC6/AC6/AC1OUT/TCK_12") (pintype "bidirectional"))
    )
    (net (code "66") (name "unconnected-(U1A-PB7{slash}SYNC{slash}ADC15{slash}ADC7{slash}AC7{slash}AC0OUT{slash}TDO-Pad13)") (class "Default")
      (node (ref "U1") (pin "13") (pinfunction "PB7/SYNC/ADC15/ADC7/AC7/AC0OUT/TDO_13") (pintype "bidirectional"))
    )
    (net (code "67") (name "unconnected-(U1A-PC6{slash}SYNC{slash}OC0DLS{slash}RXD1{slash}MISO{slash}RTCOUT-Pad22)") (class "Default")
      (node (ref "U1") (pin "22") (pinfunction "PC6/SYNC/OC0DLS/RXD1/MISO/RTCOUT_22") (pintype "bidirectional"))
    )
    (net (code "68") (name "unconnected-(U1A-PD5{slash}SYNC{slash}OC1B{slash}XCK1{slash}MOSI-Pad31)") (class "Default")
      (node (ref "U1") (pin "31") (pinfunction "PD5/SYNC/OC1B/XCK1/MOSI_31") (pintype "bidirectional"))
    )
    (net (code "69") (name "unconnected-(U1A-PE5{slash}SYNC{slash}OC0CHS{slash}OC1B{slash}XCK1{slash}MOSI-Pad41)") (class "Default")
      (node (ref "U1") (pin "41") (pinfunction "PE5/SYNC/OC0CHS/OC1B/XCK1/MOSI_41") (pintype "bidirectional"))
    )
    (net (code "70") (name "unconnected-(U1A-PR1{slash}SYNC{slash}XTAL1-Pad59)") (class "Default")
      (node (ref "U1") (pin "59") (pinfunction "PR1/SYNC/XTAL1_59") (pintype "bidirectional"))
    )
    (net (code "71") (name "unconnected-(U1A-PRO{slash}SYNC{slash}XTAL2-Pad58)") (class "Default")
      (node (ref "U1") (pin "58") (pinfunction "PRO/SYNC/XTAL2_58") (pintype "bidirectional"))
    )
  )
)
